# ProPrj_USB_hub_2026-05-25.net
KiCad netlist of a schematic drawn in EasyEDA Pro
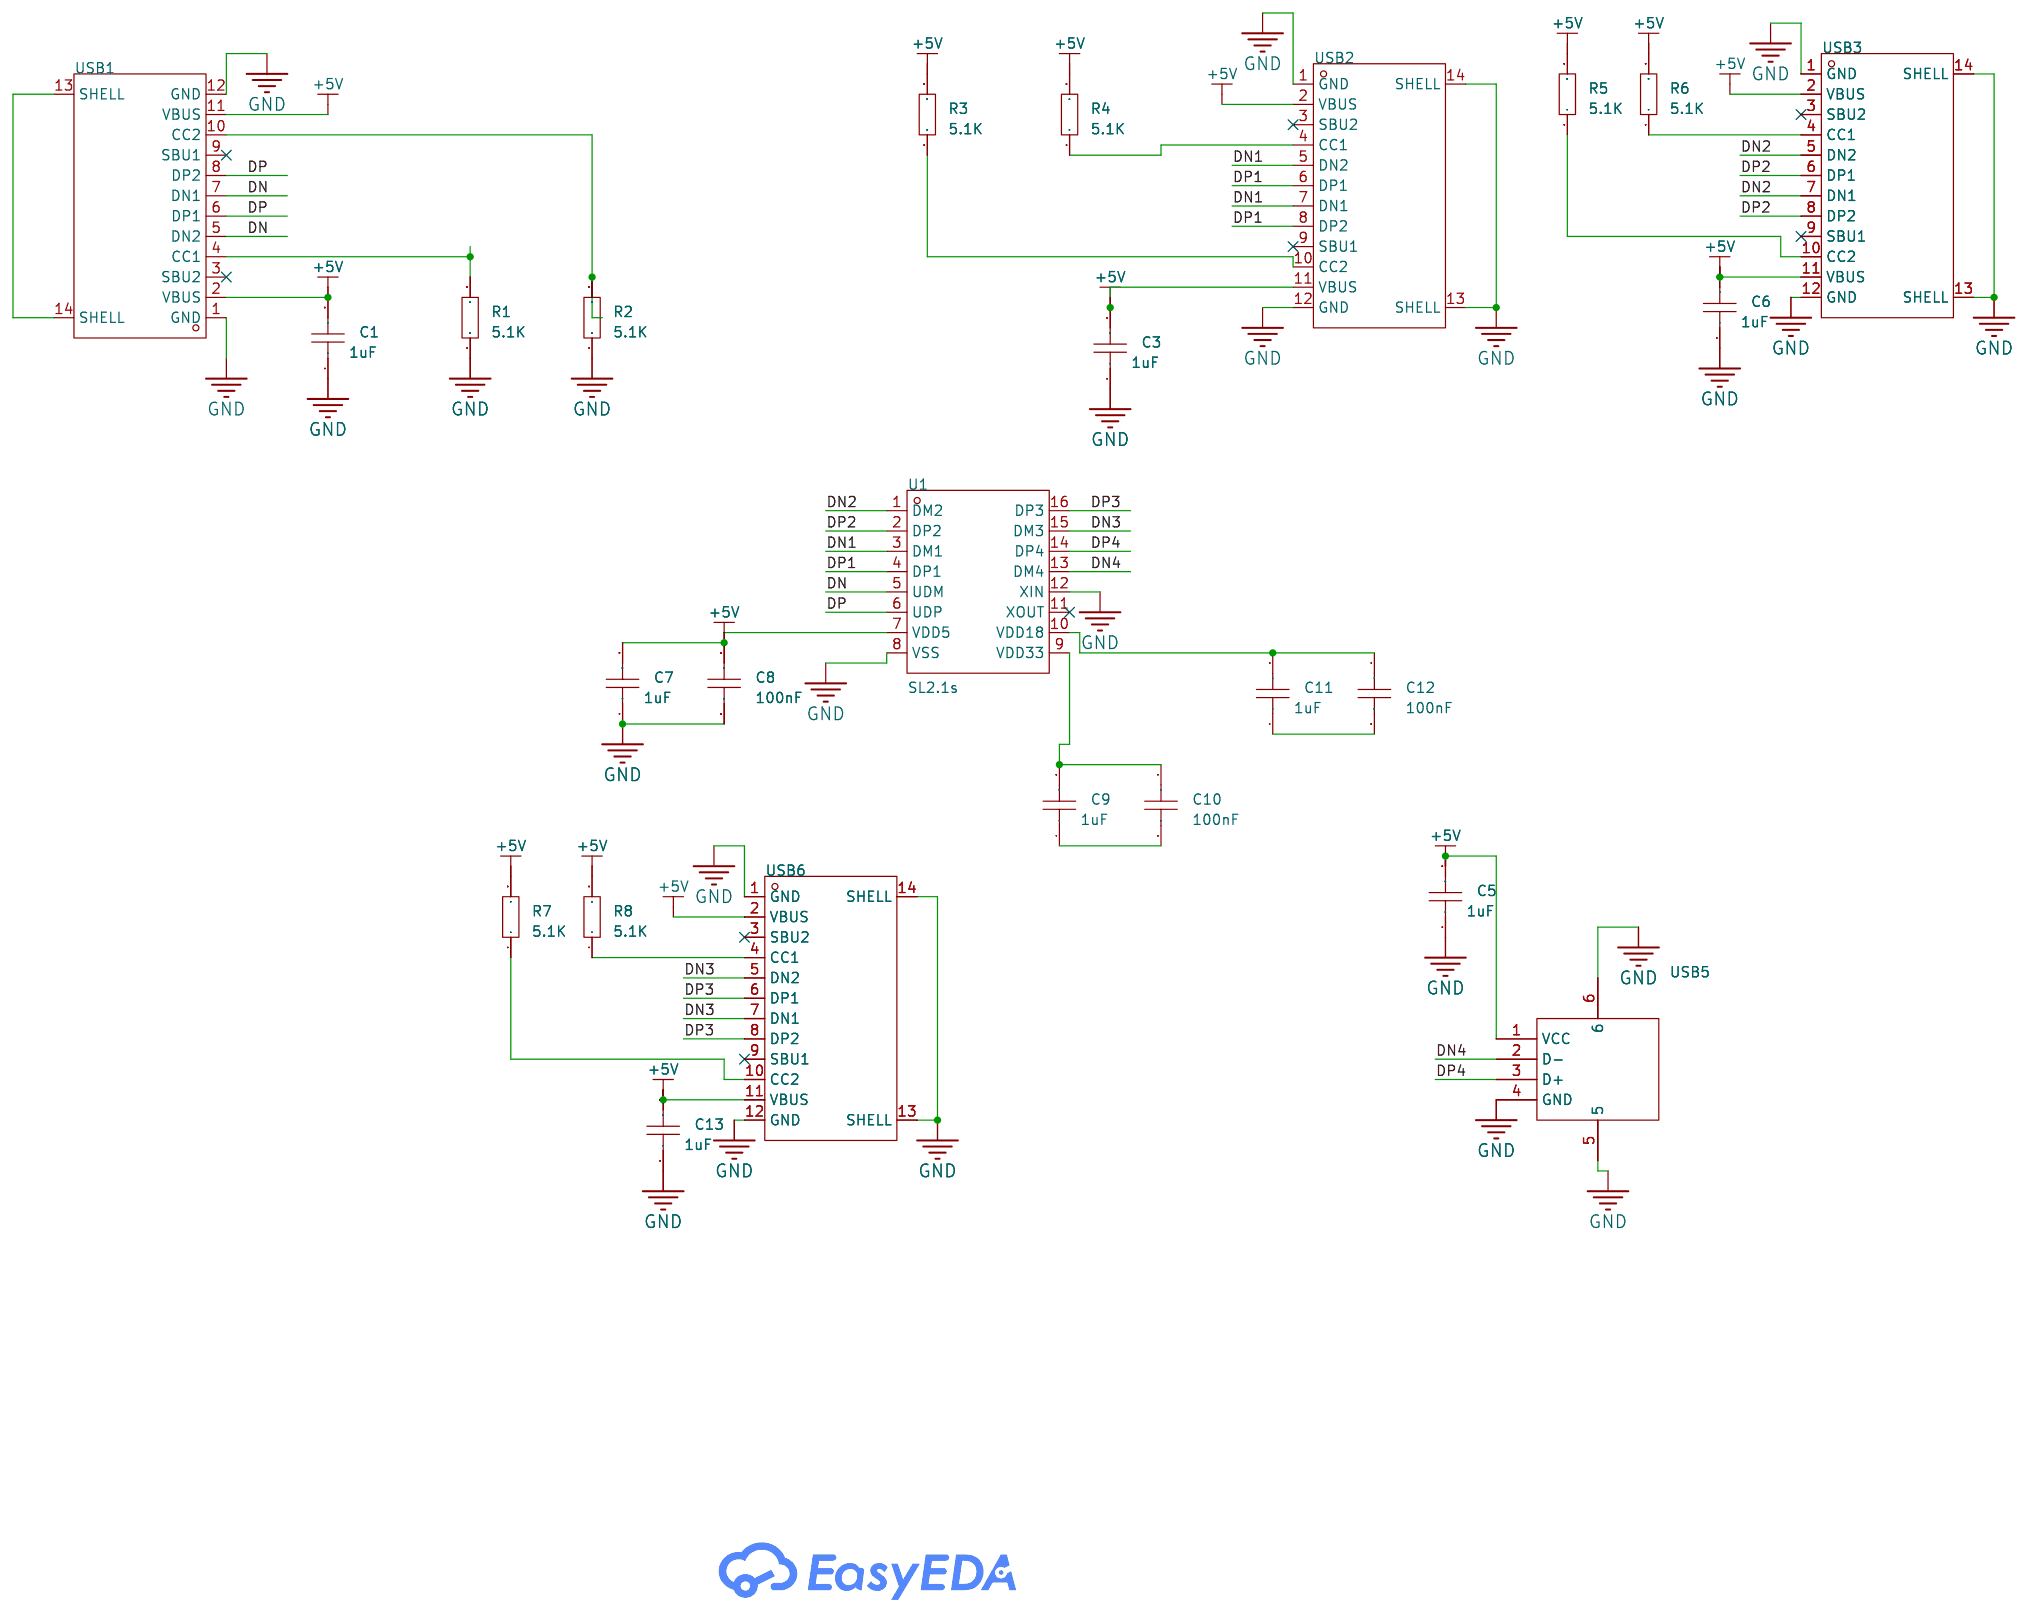
[diagram p0: schematic sheet]

(export (version "E")
  (design (tool "Eeschema 10.0.6"))
  (components
    (comp (ref "C1") (value "1uF") (footprint "easyedapro:C0603") (libsource (lib "easyedapro") (part "CAP")))
    (comp (ref "C3") (value "1uF") (footprint "easyedapro:C0603") (libsource (lib "easyedapro") (part "CAP")))
    (comp (ref "C5") (value "1uF") (footprint "easyedapro:C0603") (libsource (lib "easyedapro") (part "CAP")))
    (comp (ref "C6") (value "1uF") (footprint "easyedapro:C0603") (libsource (lib "easyedapro") (part "CAP")))
    (comp (ref "C7") (value "1uF") (footprint "easyedapro:C0603") (libsource (lib "easyedapro") (part "CAP")))
    (comp (ref "C8")
      (value "100nF")
      (footprint "easyedapro:C0603")
      (libsource (lib "easyedapro") (part "CAP"))
    )
    (comp (ref "C9") (value "1uF") (footprint "easyedapro:C0603") (libsource (lib "easyedapro") (part "CAP")))
    (comp (ref "C10")
      (value "100nF")
      (footprint "easyedapro:C0603")
      (libsource (lib "easyedapro") (part "CAP"))
    )
    (comp (ref "C11")
      (value "1uF")
      (footprint "easyedapro:C0603")
      (libsource (lib "easyedapro") (part "CAP"))
    )
    (comp (ref "C12")
      (value "100nF")
      (footprint "easyedapro:C0603")
      (libsource (lib "easyedapro") (part "CAP"))
    )
    (comp (ref "C13")
      (value "1uF")
      (footprint "easyedapro:C0603")
      (libsource (lib "easyedapro") (part "CAP"))
    )
    (comp (ref "R1")
      (value "5.1K")
      (footprint "easyedapro:R0603")
      (libsource (lib "easyedapro") (part "Res"))
    )
    (comp (ref "R2")
      (value "5.1K")
      (footprint "easyedapro:R0603")
      (libsource (lib "easyedapro") (part "Res"))
    )
    (comp (ref "R3")
      (value "5.1K")
      (footprint "easyedapro:R0603")
      (libsource (lib "easyedapro") (part "Res"))
    )
    (comp (ref "R4")
      (value "5.1K")
      (footprint "easyedapro:R0603")
      (libsource (lib "easyedapro") (part "Res"))
    )
    (comp (ref "R5")
      (value "5.1K")
      (footprint "easyedapro:R0603")
      (libsource (lib "easyedapro") (part "Res"))
    )
    (comp (ref "R6")
      (value "5.1K")
      (footprint "easyedapro:R0603")
      (libsource (lib "easyedapro") (part "Res"))
    )
    (comp (ref "R7")
      (value "5.1K")
      (footprint "easyedapro:R0603")
      (libsource (lib "easyedapro") (part "Res"))
    )
    (comp (ref "R8")
      (value "5.1K")
      (footprint "easyedapro:R0603")
      (libsource (lib "easyedapro") (part "Res"))
    )
    (comp (ref "U1")
      (value "SL2.1s")
      (footprint "easyedapro:SSOP-16_L4.6-W2.6-P0.53-LS4.0-BL")
      (fields (field (name "Manufacturer") "CoreChips(和芯润德)"))
      (libsource (lib "easyedapro") (part "SL2.1S"))
    )
    (comp (ref "USB1")
      (value "TYPE-C 16PIN 2MD(073)")
      (footprint "easyedapro:USB-C-SMD_TYPE-C-6PIN-2MD-073")
      (fields (field (name "Manufacturer") "SHOU HAN(首韩)"))
      (libsource (lib "easyedapro") (part "TYPE-C 16PIN 2MD(073)"))
    )
    (comp (ref "USB2")
      (value "TYPE-C 16PIN 2MD(073)")
      (footprint "easyedapro:USB-C-SMD_TYPE-C-6PIN-2MD-073")
      (fields (field (name "Manufacturer") "SHOU HAN(首韩)"))
      (libsource (lib "easyedapro") (part "TYPE-C 16PIN 2MD(073)"))
    )
    (comp (ref "USB3")
      (value "TYPE-C 16PIN 2MD(073)")
      (footprint "easyedapro:USB-C-SMD_TYPE-C-6PIN-2MD-073")
      (fields (field (name "Manufacturer") "SHOU HAN(首韩)"))
      (libsource (lib "easyedapro") (part "TYPE-C 16PIN 2MD(073)"))
    )
    (comp (ref "USB5")
      (value "10.0 QHHTZB6.3")
      (footprint "easyedapro:USB-A-TH_10.0QHHTZB6.3")
      (fields (field (name "Manufacturer") "SHOU HAN(首韩)"))
      (libsource (lib "easyedapro") (part "10.0 QHHTZB6.3"))
    )
    (comp (ref "USB6")
      (value "TYPE-C 16PIN 2MD(073)")
      (footprint "easyedapro:USB-C-SMD_TYPE-C-6PIN-2MD-073")
      (fields (field (name "Manufacturer") "SHOU HAN(首韩)"))
      (libsource (lib "easyedapro") (part "TYPE-C 16PIN 2MD(073)"))
    )
  )
  (nets
    (net (code "1") (name "+5V") (class "Default")
      (node (ref "C1") (pin "2") (pinfunction "2_2") (pintype "input"))
      (node (ref "C13") (pin "2") (pinfunction "2_2") (pintype "input"))
      (node (ref "C3") (pin "2") (pinfunction "2_2") (pintype "input"))
      (node (ref "C5") (pin "2") (pinfunction "2_2") (pintype "input"))
      (node (ref "C6") (pin "2") (pinfunction "2_2") (pintype "input"))
      (node (ref "C7") (pin "2") (pinfunction "2_2") (pintype "input"))
      (node (ref "C8") (pin "1") (pinfunction "1_1") (pintype "input"))
      (node (ref "R3") (pin "2") (pinfunction "2_2") (pintype "input"))
      (node (ref "R4") (pin "2") (pinfunction "2_2") (pintype "input"))
      (node (ref "R5") (pin "2") (pinfunction "2_2") (pintype "input"))
      (node (ref "R6") (pin "2") (pinfunction "2_2") (pintype "input"))
      (node (ref "R7") (pin "2") (pinfunction "2_2") (pintype "input"))
      (node (ref "R8") (pin "2") (pinfunction "2_2") (pintype "input"))
      (node (ref "U1") (pin "7") (pinfunction "VDD5_7") (pintype "unspecified"))
      (node (ref "USB1") (pin "11") (pinfunction "VBUS_11") (pintype "unspecified"))
      (node (ref "USB1") (pin "2") (pinfunction "VBUS_2") (pintype "unspecified"))
      (node (ref "USB2") (pin "11") (pinfunction "VBUS_11") (pintype "unspecified"))
      (node (ref "USB2") (pin "2") (pinfunction "VBUS_2") (pintype "unspecified"))
      (node (ref "USB3") (pin "11") (pinfunction "VBUS_11") (pintype "unspecified"))
      (node (ref "USB3") (pin "2") (pinfunction "VBUS_2") (pintype "unspecified"))
      (node (ref "USB5") (pin "1") (pinfunction "VCC_1") (pintype "unspecified"))
      (node (ref "USB6") (pin "11") (pinfunction "VBUS_11") (pintype "unspecified"))
      (node (ref "USB6") (pin "2") (pinfunction "VBUS_2") (pintype "unspecified"))
    )
    (net (code "2") (name "/DN") (class "Default")
      (node (ref "U1") (pin "5") (pinfunction "UDM_5") (pintype "unspecified"))
      (node (ref "USB1") (pin "5") (pinfunction "DN2_5") (pintype "unspecified"))
      (node (ref "USB1") (pin "7") (pinfunction "DN1_7") (pintype "unspecified"))
    )
    (net (code "3") (name "/DN1") (class "Default")
      (node (ref "U1") (pin "3") (pinfunction "DM1_3") (pintype "unspecified"))
      (node (ref "USB2") (pin "5") (pinfunction "DN2_5") (pintype "unspecified"))
      (node (ref "USB2") (pin "7") (pinfunction "DN1_7") (pintype "unspecified"))
    )
    (net (code "4") (name "/DN2") (class "Default")
      (node (ref "U1") (pin "1") (pinfunction "DM2_1") (pintype "unspecified"))
      (node (ref "USB3") (pin "5") (pinfunction "DN2_5") (pintype "unspecified"))
      (node (ref "USB3") (pin "7") (pinfunction "DN1_7") (pintype "unspecified"))
    )
    (net (code "5") (name "/DN3") (class "Default")
      (node (ref "U1") (pin "15") (pinfunction "DM3_15") (pintype "unspecified"))
      (node (ref "USB6") (pin "5") (pinfunction "DN2_5") (pintype "unspecified"))
      (node (ref "USB6") (pin "7") (pinfunction "DN1_7") (pintype "unspecified"))
    )
    (net (code "6") (name "/DN4") (class "Default")
      (node (ref "U1") (pin "13") (pinfunction "DM4_13") (pintype "unspecified"))
      (node (ref "USB5") (pin "2") (pinfunction "D-_2") (pintype "unspecified"))
    )
    (net (code "7") (name "/DP") (class "Default")
      (node (ref "U1") (pin "6") (pinfunction "UDP_6") (pintype "unspecified"))
      (node (ref "USB1") (pin "6") (pinfunction "DP1_6") (pintype "unspecified"))
      (node (ref "USB1") (pin "8") (pinfunction "DP2_8") (pintype "unspecified"))
    )
    (net (code "8") (name "/DP1") (class "Default")
      (node (ref "U1") (pin "4") (pinfunction "DP1_4") (pintype "unspecified"))
      (node (ref "USB2") (pin "6") (pinfunction "DP1_6") (pintype "unspecified"))
      (node (ref "USB2") (pin "8") (pinfunction "DP2_8") (pintype "unspecified"))
    )
    (net (code "9") (name "/DP2") (class "Default")
      (node (ref "U1") (pin "2") (pinfunction "DP2_2") (pintype "unspecified"))
      (node (ref "USB3") (pin "6") (pinfunction "DP1_6") (pintype "unspecified"))
      (node (ref "USB3") (pin "8") (pinfunction "DP2_8") (pintype "unspecified"))
    )
    (net (code "10") (name "/DP3") (class "Default")
      (node (ref "U1") (pin "16") (pinfunction "DP3_16") (pintype "unspecified"))
      (node (ref "USB6") (pin "6") (pinfunction "DP1_6") (pintype "unspecified"))
      (node (ref "USB6") (pin "8") (pinfunction "DP2_8") (pintype "unspecified"))
    )
    (net (code "11") (name "/DP4") (class "Default")
      (node (ref "U1") (pin "14") (pinfunction "DP4_14") (pintype "unspecified"))
      (node (ref "USB5") (pin "3") (pinfunction "D+_3") (pintype "unspecified"))
    )
    (net (code "12") (name "GND") (class "Default")
      (node (ref "C1") (pin "1") (pinfunction "1_1") (pintype "input"))
      (node (ref "C13") (pin "1") (pinfunction "1_1") (pintype "input"))
      (node (ref "C3") (pin "1") (pinfunction "1_1") (pintype "input"))
      (node (ref "C5") (pin "1") (pinfunction "1_1") (pintype "input"))
      (node (ref "C6") (pin "1") (pinfunction "1_1") (pintype "input"))
      (node (ref "C7") (pin "1") (pinfunction "1_1") (pintype "input"))
      (node (ref "C8") (pin "2") (pinfunction "2_2") (pintype "input"))
      (node (ref "R1") (pin "1") (pinfunction "1_1") (pintype "input"))
      (node (ref "R2") (pin "1") (pinfunction "1_1") (pintype "input"))
      (node (ref "U1") (pin "12") (pinfunction "XIN_12") (pintype "unspecified"))
      (node (ref "U1") (pin "8") (pinfunction "VSS_8") (pintype "unspecified"))
      (node (ref "USB1") (pin "1") (pinfunction "GND_1") (pintype "unspecified"))
      (node (ref "USB1") (pin "12") (pinfunction "GND_12") (pintype "unspecified"))
      (node (ref "USB2") (pin "1") (pinfunction "GND_1") (pintype "unspecified"))
      (node (ref "USB2") (pin "12") (pinfunction "GND_12") (pintype "unspecified"))
      (node (ref "USB2") (pin "13") (pinfunction "SHELL_13") (pintype "unspecified"))
      (node (ref "USB2") (pin "14") (pinfunction "SHELL_14") (pintype "unspecified"))
      (node (ref "USB3") (pin "1") (pinfunction "GND_1") (pintype "unspecified"))
      (node (ref "USB3") (pin "12") (pinfunction "GND_12") (pintype "unspecified"))
      (node (ref "USB3") (pin "13") (pinfunction "SHELL_13") (pintype "unspecified"))
      (node (ref "USB3") (pin "14") (pinfunction "SHELL_14") (pintype "unspecified"))
      (node (ref "USB5") (pin "4") (pinfunction "GND_4") (pintype "unspecified"))
      (node (ref "USB5") (pin "5") (pinfunction "5_5") (pintype "unspecified"))
      (node (ref "USB5") (pin "6") (pinfunction "6_6") (pintype "unspecified"))
      (node (ref "USB6") (pin "1") (pinfunction "GND_1") (pintype "unspecified"))
      (node (ref "USB6") (pin "12") (pinfunction "GND_12") (pintype "unspecified"))
      (node (ref "USB6") (pin "13") (pinfunction "SHELL_13") (pintype "unspecified"))
      (node (ref "USB6") (pin "14") (pinfunction "SHELL_14") (pintype "unspecified"))
    )
    (net (code "13") (name "Net-(C10-Pad2)") (class "Default")
      (node (ref "C10") (pin "2") (pinfunction "2_2") (pintype "input"))
      (node (ref "C9") (pin "1") (pinfunction "1_1") (pintype "input"))
    )
    (net (code "14") (name "Net-(C11-Pad1)") (class "Default")
      (node (ref "C11") (pin "1") (pinfunction "1_1") (pintype "input"))
      (node (ref "C12") (pin "2") (pinfunction "2_2") (pintype "input"))
    )
    (net (code "15") (name "Net-(U1-VDD18)") (class "Default")
      (node (ref "C11") (pin "2") (pinfunction "2_2") (pintype "input"))
      (node (ref "C12") (pin "1") (pinfunction "1_1") (pintype "input"))
      (node (ref "U1") (pin "10") (pinfunction "VDD18_10") (pintype "unspecified"))
    )
    (net (code "16") (name "Net-(U1-VDD33)") (class "Default")
      (node (ref "C10") (pin "1") (pinfunction "1_1") (pintype "input"))
      (node (ref "C9") (pin "2") (pinfunction "2_2") (pintype "input"))
      (node (ref "U1") (pin "9") (pinfunction "VDD33_9") (pintype "unspecified"))
    )
    (net (code "17") (name "Net-(USB1-CC1)") (class "Default")
      (node (ref "R1") (pin "2") (pinfunction "2_2") (pintype "input"))
      (node (ref "USB1") (pin "4") (pinfunction "CC1_4") (pintype "unspecified"))
    )
    (net (code "18") (name "Net-(USB1-CC2)") (class "Default")
      (node (ref "R2") (pin "2") (pinfunction "2_2") (pintype "input"))
      (node (ref "USB1") (pin "10") (pinfunction "CC2_10") (pintype "unspecified"))
    )
    (net (code "19") (name "Net-(USB1-SHELL-Pad13)") (class "Default")
      (node (ref "USB1") (pin "13") (pinfunction "SHELL_13") (pintype "unspecified"))
      (node (ref "USB1") (pin "14") (pinfunction "SHELL_14") (pintype "unspecified"))
    )
    (net (code "20") (name "Net-(USB2-CC1)") (class "Default")
      (node (ref "R4") (pin "1") (pinfunction "1_1") (pintype "input"))
      (node (ref "USB2") (pin "4") (pinfunction "CC1_4") (pintype "unspecified"))
    )
    (net (code "21") (name "Net-(USB2-CC2)") (class "Default")
      (node (ref "R3") (pin "1") (pinfunction "1_1") (pintype "input"))
      (node (ref "USB2") (pin "10") (pinfunction "CC2_10") (pintype "unspecified"))
    )
    (net (code "22") (name "Net-(USB3-CC1)") (class "Default")
      (node (ref "R6") (pin "1") (pinfunction "1_1") (pintype "input"))
      (node (ref "USB3") (pin "4") (pinfunction "CC1_4") (pintype "unspecified"))
    )
    (net (code "23") (name "Net-(USB3-CC2)") (class "Default")
      (node (ref "R5") (pin "1") (pinfunction "1_1") (pintype "input"))
      (node (ref "USB3") (pin "10") (pinfunction "CC2_10") (pintype "unspecified"))
    )
    (net (code "24") (name "Net-(USB6-CC1)") (class "Default")
      (node (ref "R8") (pin "1") (pinfunction "1_1") (pintype "input"))
      (node (ref "USB6") (pin "4") (pinfunction "CC1_4") (pintype "unspecified"))
    )
    (net (code "25") (name "Net-(USB6-CC2)") (class "Default")
      (node (ref "R7") (pin "1") (pinfunction "1_1") (pintype "input"))
      (node (ref "USB6") (pin "10") (pinfunction "CC2_10") (pintype "unspecified"))
    )
    (net (code "26") (name "unconnected-(U1-XOUT-Pad11)") (class "Default")
      (node (ref "U1") (pin "11") (pinfunction "XOUT_11") (pintype "unspecified+no_connect"))
    )
    (net (code "27") (name "unconnected-(USB1-SBU1-Pad9)") (class "Default")
      (node (ref "USB1") (pin "9") (pinfunction "SBU1_9") (pintype "unspecified+no_connect"))
    )
    (net (code "28") (name "unconnected-(USB1-SBU2-Pad3)") (class "Default")
      (node (ref "USB1") (pin "3") (pinfunction "SBU2_3") (pintype "unspecified+no_connect"))
    )
    (net (code "29") (name "unconnected-(USB2-SBU1-Pad9)") (class "Default")
      (node (ref "USB2") (pin "9") (pinfunction "SBU1_9") (pintype "unspecified+no_connect"))
    )
    (net (code "30") (name "unconnected-(USB2-SBU2-Pad3)") (class "Default")
      (node (ref "USB2") (pin "3") (pinfunction "SBU2_3") (pintype "unspecified+no_connect"))
    )
    (net (code "31") (name "unconnected-(USB3-SBU1-Pad9)") (class "Default")
      (node (ref "USB3") (pin "9") (pinfunction "SBU1_9") (pintype "unspecified+no_connect"))
    )
    (net (code "32") (name "unconnected-(USB3-SBU2-Pad3)") (class "Default")
      (node (ref "USB3") (pin "3") (pinfunction "SBU2_3") (pintype "unspecified+no_connect"))
    )
    (net (code "33") (name "unconnected-(USB6-SBU1-Pad9)") (class "Default")
      (node (ref "USB6") (pin "9") (pinfunction "SBU1_9") (pintype "unspecified+no_connect"))
    )
    (net (code "34") (name "unconnected-(USB6-SBU2-Pad3)") (class "Default")
      (node (ref "USB6") (pin "3") (pinfunction "SBU2_3") (pintype "unspecified+no_connect"))
    )
  )
)
